# Sheet1.net
KiCad netlist of a schematic drawn in Altium Designer
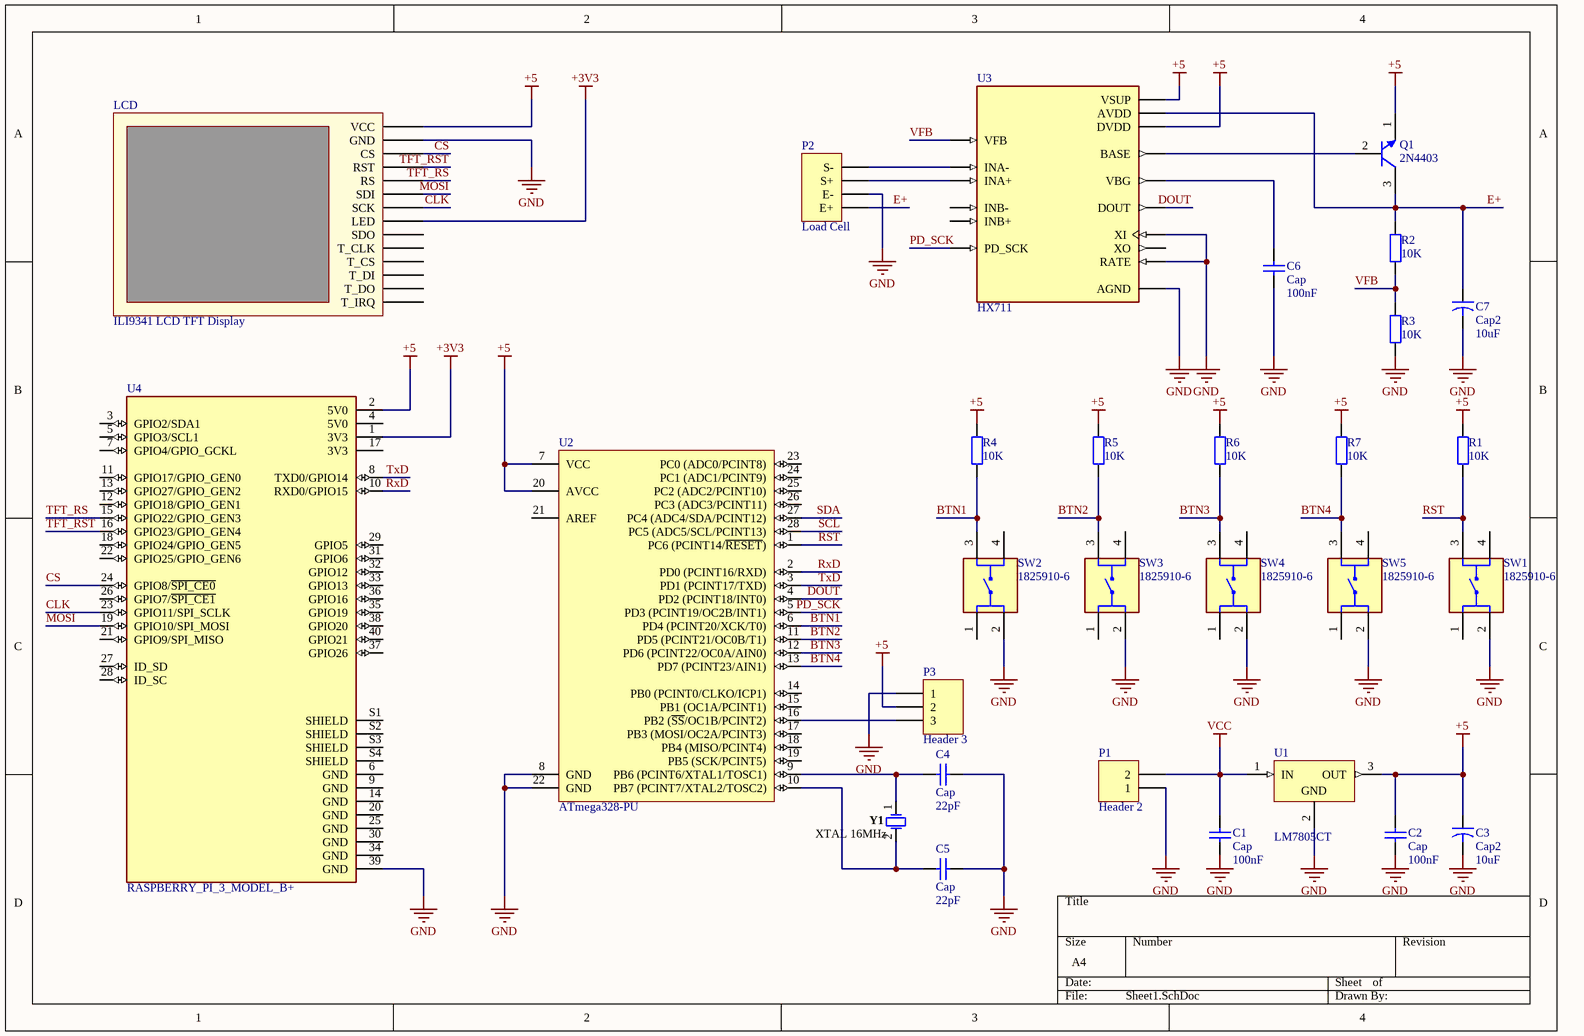
[diagram p0: Sheet1.SchDoc]

(export (version "E")
  (design (tool "Eeschema 10.0.6"))
  (components
    (comp (ref "C1")
      (value "Cap")
      (footprint "RAD-0.2")
      (description "Capacitor")
      (fields (field (name "ALTIUM_VALUE") "100nF") (field (name "PUBLISHER") "Altium Limited"))
      (libsource (lib "Miscellaneous Devices") (part "Cap"))
    )
    (comp (ref "C2")
      (value "Cap")
      (footprint "RAD-0.2")
      (description "Capacitor")
      (fields (field (name "ALTIUM_VALUE") "100nF") (field (name "PUBLISHER") "Altium Limited"))
      (libsource (lib "Miscellaneous Devices") (part "Cap"))
    )
    (comp (ref "C3")
      (value "Cap2")
      (footprint "R38")
      (description "Capacitor")
      (fields (field (name "ALTIUM_VALUE") "10uF") (field (name "PUBLISHER") "Altium Limited"))
      (libsource (lib "Miscellaneous Devices") (part "Cap2"))
    )
    (comp (ref "C4")
      (value "Cap")
      (footprint "RAD-0.1")
      (description "Capacitor")
      (fields (field (name "ALTIUM_VALUE") "22pF") (field (name "PUBLISHER") "Altium Limited"))
      (libsource (lib "Miscellaneous Devices") (part "Cap"))
    )
    (comp (ref "C5")
      (value "Cap")
      (footprint "RAD-0.1")
      (description "Capacitor")
      (fields (field (name "ALTIUM_VALUE") "22pF") (field (name "PUBLISHER") "Altium Limited"))
      (libsource (lib "Miscellaneous Devices") (part "Cap"))
    )
    (comp (ref "C6")
      (value "Cap")
      (footprint "RAD-0.2")
      (description "Capacitor")
      (fields (field (name "ALTIUM_VALUE") "100nF") (field (name "PUBLISHER") "Altium Limited"))
      (libsource (lib "Miscellaneous Devices") (part "Cap"))
    )
    (comp (ref "C7")
      (value "Cap2")
      (footprint "R38")
      (description "Capacitor")
      (fields (field (name "ALTIUM_VALUE") "10uF") (field (name "PUBLISHER") "Altium Limited"))
      (libsource (lib "Miscellaneous Devices") (part "Cap2"))
    )
    (comp (ref "LCD")
      (value "ILI9341 LCD TFT Display")
      (footprint "ILI9341")
      (libsource (lib "ILI9341") (part "ILI9341"))
    )
    (comp (ref "P1")
      (value "Header 2")
      (footprint "HDR1X2")
      (description "Header, 2-Pin")
      (fields (field (name "PUBLISHER") "Altium Limited"))
      (libsource (lib "Miscellaneous Connectors") (part "Header 2"))
    )
    (comp (ref "P2")
      (value "Load Cell")
      (footprint "HDR1X4")
      (description "Load Cell Connector, 4-Pin")
      (fields (field (name "PUBLISHER") "Altium Limited"))
      (libsource (lib "Miscellaneous Connectors") (part "Header 4"))
    )
    (comp (ref "P3")
      (value "Header 3")
      (footprint "HDR1X3")
      (description "Header, 3-Pin")
      (fields (field (name "PUBLISHER") "Altium Limited"))
      (libsource (lib "Miscellaneous Connectors") (part "Header 3"))
    )
    (comp (ref "Q1")
      (value "2N4403")
      (footprint "ONSC-TO-92-3-29-11_AM_BL")
      (description "General Purpose Transistor, NPN Silicon, 3-Pin TO-92, Pb-Free, Ammo Box")
      (fields (field (name "PARTNUMBER") "2N4401RLRPG") (field (name "MANUFACTURER") "On Semiconductor"))
      (libsource (lib "Altium Content Vault") (part "ONSC-NPN-E1B2C3-3"))
    )
    (comp (ref "R1")
      (value "10K")
      (footprint "AXIAL-0.4")
      (description "Resistor")
      (fields (field (name "PUBLISHER") "Altium Limited"))
      (libsource (lib "Miscellaneous Devices") (part "Res2"))
    )
    (comp (ref "R2")
      (value "10K")
      (footprint "AXIAL-0.4")
      (description "Resistor")
      (fields (field (name "PUBLISHER") "Altium Limited"))
      (libsource (lib "Miscellaneous Devices") (part "Res2"))
    )
    (comp (ref "R3")
      (value "10K")
      (footprint "AXIAL-0.4")
      (description "Resistor")
      (fields (field (name "PUBLISHER") "Altium Limited"))
      (libsource (lib "Miscellaneous Devices") (part "Res2"))
    )
    (comp (ref "R4")
      (value "10K")
      (footprint "AXIAL-0.4")
      (description "Resistor")
      (fields (field (name "PUBLISHER") "Altium Limited"))
      (libsource (lib "Miscellaneous Devices") (part "Res2"))
    )
    (comp (ref "R5")
      (value "10K")
      (footprint "AXIAL-0.4")
      (description "Resistor")
      (fields (field (name "PUBLISHER") "Altium Limited"))
      (libsource (lib "Miscellaneous Devices") (part "Res2"))
    )
    (comp (ref "R6")
      (value "10K")
      (footprint "AXIAL-0.4")
      (description "Resistor")
      (fields (field (name "PUBLISHER") "Altium Limited"))
      (libsource (lib "Miscellaneous Devices") (part "Res2"))
    )
    (comp (ref "R7")
      (value "10K")
      (footprint "AXIAL-0.4")
      (description "Resistor")
      (fields (field (name "PUBLISHER") "Altium Limited"))
      (libsource (lib "Miscellaneous Devices") (part "Res2"))
    )
    (comp (ref "SW1")
      (value "1825910-6")
      (footprint "SW_1825910-6-4")
      (description "Switch Tactile OFF (ON) SPST Round Button PC Pins 0.05A 24VDC 100000Cycles 1.57N Thru-Hole Loose")
      (libsource (lib "1825910-6") (part "1825910-6"))
    )
    (comp (ref "SW2")
      (value "1825910-6")
      (footprint "SW_1825910-6-4")
      (description "Switch Tactile OFF (ON) SPST Round Button PC Pins 0.05A 24VDC 100000Cycles 1.57N Thru-Hole Loose")
      (libsource (lib "1825910-6") (part "1825910-6"))
    )
    (comp (ref "SW3")
      (value "1825910-6")
      (footprint "SW_1825910-6-4")
      (description "Switch Tactile OFF (ON) SPST Round Button PC Pins 0.05A 24VDC 100000Cycles 1.57N Thru-Hole Loose")
      (libsource (lib "1825910-6") (part "1825910-6"))
    )
    (comp (ref "SW4")
      (value "1825910-6")
      (footprint "SW_1825910-6-4")
      (description "Switch Tactile OFF (ON) SPST Round Button PC Pins 0.05A 24VDC 100000Cycles 1.57N Thru-Hole Loose")
      (libsource (lib "1825910-6") (part "1825910-6"))
    )
    (comp (ref "SW5")
      (value "1825910-6")
      (footprint "SW_1825910-6-4")
      (description "Switch Tactile OFF (ON) SPST Round Button PC Pins 0.05A 24VDC 100000Cycles 1.57N Thru-Hole Loose")
      (libsource (lib "1825910-6") (part "1825910-6"))
    )
    (comp (ref "U1")
      (value "LM7805CT")
      (footprint "FAIR-TO-220-3")
      (description "Positive Voltage Regulator, 5 V, 1 A, -40 to 125 degC, 3-Pin TO-220, RoHS, Tube")
      (fields (field (name "MANUFACTURER") "FairchildSemiconductor"))
      (libsource (lib "Altium Content Vault") (part "FAIR-LM7805CT-TO220-3"))
    )
    (comp (ref "U2")
      (value "ATmega328-PU")
      (footprint "28P3")
      (libsource (lib "Altium Content Vault") (part "MC-8B-ATM48-IL28"))
    )
    (comp (ref "U3")
      (value "HX711")
      (footprint "SOP127P600X180-16N")
      (libsource (lib "HX711") (part "HX711"))
    )
    (comp (ref "U4")
      (value "RASPBERRY_PI_3_MODEL_B+")
      (footprint "MODULE_RASPBERRY_PI_3_MODEL_B+")
      (description "BCM2835 Raspberry Pi Model B+ - ARM11, VideoCore MPU Embedded Evaluation Board")
      (libsource (lib "RASPBERRY_PI_3_MODEL_B_") (part "RASPBERRY_PI_3_MODEL_B+"))
    )
    (comp (ref "Y1")
      (value "XTAL 16MHz")
      (footprint "FOX-FOXSLF-2_V")
      (description "Resistance Weld Thru-Hole Crystal, 12 MHz, +/-30 ppm, -20 to 70 degC, 2-Pin THD, RoHS, Bulk")
      (libsource (lib "Altium Content Vault") (part "XTAL-1-2-2"))
    )
  )
  (nets
    (net (code "1") (name "+3V3") (class "Default")
      (node (ref "LCD") (pin "7") (pinfunction "LED_7") (pintype "passive"))
      (node (ref "U4") (pin "1") (pinfunction "3V3_1") (pintype "power_in"))
    )
    (net (code "2") (name "+5") (class "Default")
      (node (ref "C2") (pin "2") (pinfunction "2_2") (pintype "passive"))
      (node (ref "C3") (pin "1") (pinfunction "1_1") (pintype "passive"))
      (node (ref "LCD") (pin "0") (pinfunction "VCC_0") (pintype "passive"))
      (node (ref "P3") (pin "2") (pinfunction "2_2") (pintype "passive"))
      (node (ref "Q1") (pin "1") (pinfunction "E_1") (pintype "passive"))
      (node (ref "R1") (pin "2") (pinfunction "2_2") (pintype "passive"))
      (node (ref "R4") (pin "2") (pinfunction "2_2") (pintype "passive"))
      (node (ref "R5") (pin "2") (pinfunction "2_2") (pintype "passive"))
      (node (ref "R6") (pin "2") (pinfunction "2_2") (pintype "passive"))
      (node (ref "R7") (pin "2") (pinfunction "2_2") (pintype "passive"))
      (node (ref "U1") (pin "3") (pinfunction "OUT_3") (pintype "output"))
      (node (ref "U2") (pin "20") (pinfunction "AVCC_20") (pintype "power_in"))
      (node (ref "U2") (pin "7") (pinfunction "VCC_7") (pintype "power_in"))
      (node (ref "U3") (pin "1") (pinfunction "VSUP_1") (pintype "power_in"))
      (node (ref "U3") (pin "16") (pinfunction "DVDD_16") (pintype "power_in"))
      (node (ref "U4") (pin "2") (pinfunction "5V0_2") (pintype "power_in"))
    )
    (net (code "3") (name "/BTN1") (class "Default")
      (node (ref "R4") (pin "1") (pinfunction "1_1") (pintype "passive"))
      (node (ref "SW2") (pin "3") (pinfunction "3_3") (pintype "passive"))
      (node (ref "U2") (pin "6") (pinfunction "PD4_(PCINT20/XCK/T0)_6") (pintype "bidirectional"))
    )
    (net (code "4") (name "/BTN2") (class "Default")
      (node (ref "R5") (pin "1") (pinfunction "1_1") (pintype "passive"))
      (node (ref "SW3") (pin "3") (pinfunction "3_3") (pintype "passive"))
      (node (ref "U2") (pin "11") (pinfunction "PD5_(PCINT21/OC0B/T1)_11") (pintype "bidirectional"))
    )
    (net (code "5") (name "/BTN3") (class "Default")
      (node (ref "R6") (pin "1") (pinfunction "1_1") (pintype "passive"))
      (node (ref "SW4") (pin "3") (pinfunction "3_3") (pintype "passive"))
      (node (ref "U2") (pin "12") (pinfunction "PD6_(PCINT22/OC0A/AIN0)_12") (pintype "bidirectional"))
    )
    (net (code "6") (name "/BTN4") (class "Default")
      (node (ref "R7") (pin "1") (pinfunction "1_1") (pintype "passive"))
      (node (ref "SW5") (pin "3") (pinfunction "3_3") (pintype "passive"))
      (node (ref "U2") (pin "13") (pinfunction "PD7_(PCINT23/AIN1)_13") (pintype "bidirectional"))
    )
    (net (code "7") (name "/CLK") (class "Default")
      (node (ref "LCD") (pin "6") (pinfunction "SCK_6") (pintype "passive"))
      (node (ref "U4") (pin "23") (pinfunction "GPIO11/SPI_SCLK_23") (pintype "bidirectional"))
    )
    (net (code "8") (name "/CS") (class "Default")
      (node (ref "LCD") (pin "2") (pinfunction "CS_2") (pintype "passive"))
      (node (ref "U4") (pin "24") (pinfunction "GPIO8/~{SPI_CE0}_24") (pintype "bidirectional"))
    )
    (net (code "9") (name "/DOUT") (class "Default")
      (node (ref "U2") (pin "4") (pinfunction "PD2_(PCINT18/INT0)_4") (pintype "bidirectional"))
      (node (ref "U3") (pin "12") (pinfunction "DOUT_12") (pintype "output"))
    )
    (net (code "10") (name "/E+") (class "Default")
      (node (ref "C7") (pin "1") (pinfunction "1_1") (pintype "passive"))
      (node (ref "P2") (pin "1") (pinfunction "E+_1") (pintype "passive"))
      (node (ref "Q1") (pin "3") (pinfunction "C_3") (pintype "passive"))
      (node (ref "R2") (pin "2") (pinfunction "2_2") (pintype "passive"))
      (node (ref "U3") (pin "3") (pinfunction "AVDD_3") (pintype "power_in"))
    )
    (net (code "11") (name "/MOSI") (class "Default")
      (node (ref "LCD") (pin "5") (pinfunction "SDI_5") (pintype "passive"))
      (node (ref "U4") (pin "19") (pinfunction "GPIO10/SPI_MOSI_19") (pintype "bidirectional"))
    )
    (net (code "12") (name "/PD_SCK") (class "Default")
      (node (ref "U2") (pin "5") (pinfunction "PD3_(PCINT19/OC2B/INT1)_5") (pintype "bidirectional"))
      (node (ref "U3") (pin "11") (pinfunction "PD_SCK_11") (pintype "input"))
    )
    (net (code "13") (name "/RST") (class "Default")
      (node (ref "R1") (pin "1") (pinfunction "1_1") (pintype "passive"))
      (node (ref "SW1") (pin "3") (pinfunction "3_3") (pintype "passive"))
      (node (ref "U2") (pin "1") (pinfunction "PC6_(PCINT14/~{RESET})_1") (pintype "bidirectional"))
    )
    (net (code "14") (name "/RxD") (class "Default")
      (node (ref "U2") (pin "2") (pinfunction "PD0_(PCINT16/RXD)_2") (pintype "bidirectional"))
      (node (ref "U4") (pin "10") (pinfunction "RXD0/GPIO15_10") (pintype "bidirectional"))
    )
    (net (code "15") (name "/SCL") (class "Default")
      (node (ref "U2") (pin "28") (pinfunction "PC5_(ADC5/SCL/PCINT13)_28") (pintype "bidirectional"))
    )
    (net (code "16") (name "/SDA") (class "Default")
      (node (ref "U2") (pin "27") (pinfunction "PC4_(ADC4/SDA/PCINT12)_27") (pintype "bidirectional"))
    )
    (net (code "17") (name "/TFT_RS") (class "Default")
      (node (ref "LCD") (pin "4") (pinfunction "RS_4") (pintype "passive"))
      (node (ref "U4") (pin "15") (pinfunction "GPIO22/GPIO_GEN3_15") (pintype "bidirectional"))
    )
    (net (code "18") (name "/TFT_RST") (class "Default")
      (node (ref "LCD") (pin "3") (pinfunction "RST_3") (pintype "passive"))
      (node (ref "U4") (pin "16") (pinfunction "GPIO23/GPIO_GEN4_16") (pintype "bidirectional"))
    )
    (net (code "19") (name "/TxD") (class "Default")
      (node (ref "U2") (pin "3") (pinfunction "PD1_(PCINT17/TXD)_3") (pintype "bidirectional"))
      (node (ref "U4") (pin "8") (pinfunction "TXD0/GPIO14_8") (pintype "bidirectional"))
    )
    (net (code "20") (name "/VFB") (class "Default")
      (node (ref "R2") (pin "1") (pinfunction "1_1") (pintype "passive"))
      (node (ref "R3") (pin "2") (pinfunction "2_2") (pintype "passive"))
      (node (ref "U3") (pin "4") (pinfunction "VFB_4") (pintype "input"))
    )
    (net (code "21") (name "GND") (class "Default")
      (node (ref "C1") (pin "1") (pinfunction "1_1") (pintype "passive"))
      (node (ref "C2") (pin "1") (pinfunction "1_1") (pintype "passive"))
      (node (ref "C3") (pin "2") (pinfunction "2_2") (pintype "passive"))
      (node (ref "C4") (pin "2") (pinfunction "2_2") (pintype "passive"))
      (node (ref "C5") (pin "2") (pinfunction "2_2") (pintype "passive"))
      (node (ref "C6") (pin "1") (pinfunction "1_1") (pintype "passive"))
      (node (ref "C7") (pin "2") (pinfunction "2_2") (pintype "passive"))
      (node (ref "LCD") (pin "1") (pinfunction "GND_1") (pintype "passive"))
      (node (ref "P1") (pin "1") (pinfunction "1_1") (pintype "passive"))
      (node (ref "P2") (pin "2") (pinfunction "E-_2") (pintype "passive"))
      (node (ref "P3") (pin "1") (pinfunction "1_1") (pintype "passive"))
      (node (ref "R3") (pin "1") (pinfunction "1_1") (pintype "passive"))
      (node (ref "SW1") (pin "2") (pinfunction "2_2") (pintype "passive"))
      (node (ref "SW2") (pin "2") (pinfunction "2_2") (pintype "passive"))
      (node (ref "SW3") (pin "2") (pinfunction "2_2") (pintype "passive"))
      (node (ref "SW4") (pin "2") (pinfunction "2_2") (pintype "passive"))
      (node (ref "SW5") (pin "2") (pinfunction "2_2") (pintype "passive"))
      (node (ref "U1") (pin "2") (pinfunction "GND_2") (pintype "power_in"))
      (node (ref "U2") (pin "22") (pinfunction "GND_22") (pintype "power_in"))
      (node (ref "U2") (pin "8") (pinfunction "GND_8") (pintype "power_in"))
      (node (ref "U3") (pin "14") (pinfunction "XI_14") (pintype "input"))
      (node (ref "U3") (pin "15") (pinfunction "RATE_15") (pintype "input"))
      (node (ref "U3") (pin "5") (pinfunction "AGND_5") (pintype "power_in"))
      (node (ref "U4") (pin "39") (pinfunction "GND_39") (pintype "power_in"))
    )
    (net (code "22") (name "Net-(P2-S+)") (class "Default")
      (node (ref "P2") (pin "3") (pinfunction "S+_3") (pintype "passive"))
      (node (ref "U3") (pin "8") (pinfunction "INA+_8") (pintype "input"))
    )
    (net (code "23") (name "Net-(P2-S-)") (class "Default")
      (node (ref "P2") (pin "4") (pinfunction "S-_4") (pintype "passive"))
      (node (ref "U3") (pin "7") (pinfunction "INA-_7") (pintype "input"))
    )
    (net (code "24") (name "Net-(Q1-B)") (class "Default")
      (node (ref "Q1") (pin "2") (pinfunction "B_2") (pintype "passive"))
      (node (ref "U3") (pin "2") (pinfunction "BASE_2") (pintype "output"))
    )
    (net (code "25") (name "Net-(U2-PB2_(~{SS}{slash}OC1B{slash}PCINT2))") (class "Default")
      (node (ref "P3") (pin "3") (pinfunction "3_3") (pintype "passive"))
      (node (ref "U2") (pin "16") (pinfunction "PB2_(~{SS}/OC1B/PCINT2)_16") (pintype "bidirectional"))
    )
    (net (code "26") (name "Net-(U2-PB6_(PCINT6{slash}XTAL1{slash}TOSC1))") (class "Default")
      (node (ref "C4") (pin "1") (pinfunction "1_1") (pintype "passive"))
      (node (ref "U2") (pin "9") (pinfunction "PB6_(PCINT6/XTAL1/TOSC1)_9") (pintype "bidirectional"))
      (node (ref "Y1") (pin "1") (pinfunction "1_1") (pintype "passive"))
    )
    (net (code "27") (name "Net-(U2-PB7_(PCINT7{slash}XTAL2{slash}TOSC2))") (class "Default")
      (node (ref "C5") (pin "1") (pinfunction "1_1") (pintype "passive"))
      (node (ref "U2") (pin "10") (pinfunction "PB7_(PCINT7/XTAL2/TOSC2)_10") (pintype "bidirectional"))
      (node (ref "Y1") (pin "2") (pinfunction "2_2") (pintype "passive"))
    )
    (net (code "28") (name "Net-(U3-VBG)") (class "Default")
      (node (ref "C6") (pin "2") (pinfunction "2_2") (pintype "passive"))
      (node (ref "U3") (pin "6") (pinfunction "VBG_6") (pintype "output"))
    )
    (net (code "29") (name "VCC") (class "Default")
      (node (ref "C1") (pin "2") (pinfunction "2_2") (pintype "passive"))
      (node (ref "P1") (pin "2") (pinfunction "2_2") (pintype "passive"))
      (node (ref "U1") (pin "1") (pinfunction "IN_1") (pintype "input"))
    )
    (net (code "30") (name "unconnected-(LCD-SDO-Pad8)") (class "Default")
      (node (ref "LCD") (pin "8") (pinfunction "SDO_8") (pintype "passive"))
    )
    (net (code "31") (name "unconnected-(LCD-T_CLK-Pad9)") (class "Default")
      (node (ref "LCD") (pin "9") (pinfunction "T_CLK_9") (pintype "passive"))
    )
    (net (code "32") (name "unconnected-(LCD-T_CS-Pad10)") (class "Default")
      (node (ref "LCD") (pin "10") (pinfunction "T_CS_10") (pintype "passive"))
    )
    (net (code "33") (name "unconnected-(LCD-T_DI-Pad11)") (class "Default")
      (node (ref "LCD") (pin "11") (pinfunction "T_DI_11") (pintype "passive"))
    )
    (net (code "34") (name "unconnected-(LCD-T_DO-Pad12)") (class "Default")
      (node (ref "LCD") (pin "12") (pinfunction "T_DO_12") (pintype "passive"))
    )
    (net (code "35") (name "unconnected-(LCD-T_IRQ-Pad13)") (class "Default")
      (node (ref "LCD") (pin "13") (pinfunction "T_IRQ_13") (pintype "passive"))
    )
    (net (code "36") (name "unconnected-(SW1-Pad1)") (class "Default")
      (node (ref "SW1") (pin "1") (pinfunction "1_1") (pintype "passive"))
    )
    (net (code "37") (name "unconnected-(SW1-Pad4)") (class "Default")
      (node (ref "SW1") (pin "4") (pinfunction "4_4") (pintype "passive"))
    )
    (net (code "38") (name "unconnected-(SW2-Pad1)") (class "Default")
      (node (ref "SW2") (pin "1") (pinfunction "1_1") (pintype "passive"))
    )
    (net (code "39") (name "unconnected-(SW2-Pad4)") (class "Default")
      (node (ref "SW2") (pin "4") (pinfunction "4_4") (pintype "passive"))
    )
    (net (code "40") (name "unconnected-(SW3-Pad1)") (class "Default")
      (node (ref "SW3") (pin "1") (pinfunction "1_1") (pintype "passive"))
    )
    (net (code "41") (name "unconnected-(SW3-Pad4)") (class "Default")
      (node (ref "SW3") (pin "4") (pinfunction "4_4") (pintype "passive"))
    )
    (net (code "42") (name "unconnected-(SW4-Pad1)") (class "Default")
      (node (ref "SW4") (pin "1") (pinfunction "1_1") (pintype "passive"))
    )
    (net (code "43") (name "unconnected-(SW4-Pad4)") (class "Default")
      (node (ref "SW4") (pin "4") (pinfunction "4_4") (pintype "passive"))
    )
    (net (code "44") (name "unconnected-(SW5-Pad1)") (class "Default")
      (node (ref "SW5") (pin "1") (pinfunction "1_1") (pintype "passive"))
    )
    (net (code "45") (name "unconnected-(SW5-Pad4)") (class "Default")
      (node (ref "SW5") (pin "4") (pinfunction "4_4") (pintype "passive"))
    )
    (net (code "46") (name "unconnected-(U2-AREF-Pad21)") (class "Default")
      (node (ref "U2") (pin "21") (pinfunction "AREF_21") (pintype "power_in"))
    )
    (net (code "47") (name "unconnected-(U2-PB0_(PCINT0{slash}CLKO{slash}ICP1)-Pad14)") (class "Default")
      (node (ref "U2") (pin "14") (pinfunction "PB0_(PCINT0/CLKO/ICP1)_14") (pintype "bidirectional"))
    )
    (net (code "48") (name "unconnected-(U2-PB1_(OC1A{slash}PCINT1)-Pad15)") (class "Default")
      (node (ref "U2") (pin "15") (pinfunction "PB1_(OC1A/PCINT1)_15") (pintype "bidirectional"))
    )
    (net (code "49") (name "unconnected-(U2-PB3_(MOSI{slash}OC2A{slash}PCINT3)-Pad17)") (class "Default")
      (node (ref "U2") (pin "17") (pinfunction "PB3_(MOSI/OC2A/PCINT3)_17") (pintype "bidirectional"))
    )
    (net (code "50") (name "unconnected-(U2-PB4_(MISO{slash}PCINT4)-Pad18)") (class "Default")
      (node (ref "U2") (pin "18") (pinfunction "PB4_(MISO/PCINT4)_18") (pintype "bidirectional"))
    )
    (net (code "51") (name "unconnected-(U2-PB5_(SCK{slash}PCINT5)-Pad19)") (class "Default")
      (node (ref "U2") (pin "19") (pinfunction "PB5_(SCK/PCINT5)_19") (pintype "bidirectional"))
    )
    (net (code "52") (name "unconnected-(U2-PC0_(ADC0{slash}PCINT8)-Pad23)") (class "Default")
      (node (ref "U2") (pin "23") (pinfunction "PC0_(ADC0/PCINT8)_23") (pintype "bidirectional"))
    )
    (net (code "53") (name "unconnected-(U2-PC1_(ADC1{slash}PCINT9)-Pad24)") (class "Default")
      (node (ref "U2") (pin "24") (pinfunction "PC1_(ADC1/PCINT9)_24") (pintype "bidirectional"))
    )
    (net (code "54") (name "unconnected-(U2-PC2_(ADC2{slash}PCINT10)-Pad25)") (class "Default")
      (node (ref "U2") (pin "25") (pinfunction "PC2_(ADC2/PCINT10)_25") (pintype "bidirectional"))
    )
    (net (code "55") (name "unconnected-(U2-PC3_(ADC3{slash}PCINT11)-Pad26)") (class "Default")
      (node (ref "U2") (pin "26") (pinfunction "PC3_(ADC3/PCINT11)_26") (pintype "bidirectional"))
    )
    (net (code "56") (name "unconnected-(U3-INB+-Pad10)") (class "Default")
      (node (ref "U3") (pin "10") (pinfunction "INB+_10") (pintype "input"))
    )
    (net (code "57") (name "unconnected-(U3-INB--Pad9)") (class "Default")
      (node (ref "U3") (pin "9") (pinfunction "INB-_9") (pintype "input"))
    )
    (net (code "58") (name "unconnected-(U3-XO-Pad13)") (class "Default")
      (node (ref "U3") (pin "13") (pinfunction "XO_13") (pintype "output"))
    )
    (net (code "59") (name "unconnected-(U4-3V3-Pad17)") (class "Default")
      (node (ref "U4") (pin "17") (pinfunction "3V3_17") (pintype "power_in"))
    )
    (net (code "60") (name "unconnected-(U4-5V0-Pad4)") (class "Default")
      (node (ref "U4") (pin "4") (pinfunction "5V0_4") (pintype "power_in"))
    )
    (net (code "61") (name "unconnected-(U4-GND-Pad6)") (class "Default")
      (node (ref "U4") (pin "6") (pinfunction "GND_6") (pintype "power_in"))
    )
    (net (code "62") (name "unconnected-(U4-GND-Pad9)") (class "Default")
      (node (ref "U4") (pin "9") (pinfunction "GND_9") (pintype "power_in"))
    )
    (net (code "63") (name "unconnected-(U4-GND-Pad14)") (class "Default")
      (node (ref "U4") (pin "14") (pinfunction "GND_14") (pintype "power_in"))
    )
    (net (code "64") (name "unconnected-(U4-GND-Pad20)") (class "Default")
      (node (ref "U4") (pin "20") (pinfunction "GND_20") (pintype "power_in"))
    )
    (net (code "65") (name "unconnected-(U4-GND-Pad25)") (class "Default")
      (node (ref "U4") (pin "25") (pinfunction "GND_25") (pintype "power_in"))
    )
    (net (code "66") (name "unconnected-(U4-GND-Pad30)") (class "Default")
      (node (ref "U4") (pin "30") (pinfunction "GND_30") (pintype "power_in"))
    )
    (net (code "67") (name "unconnected-(U4-GND-Pad34)") (class "Default")
      (node (ref "U4") (pin "34") (pinfunction "GND_34") (pintype "power_in"))
    )
    (net (code "68") (name "unconnected-(U4-GPIO2{slash}SDA1-Pad3)") (class "Default")
      (node (ref "U4") (pin "3") (pinfunction "GPIO2/SDA1_3") (pintype "bidirectional"))
    )
    (net (code "69") (name "unconnected-(U4-GPIO3{slash}SCL1-Pad5)") (class "Default")
      (node (ref "U4") (pin "5") (pinfunction "GPIO3/SCL1_5") (pintype "bidirectional"))
    )
    (net (code "70") (name "unconnected-(U4-GPIO4{slash}GPIO_GCKL-Pad7)") (class "Default")
      (node (ref "U4") (pin "7") (pinfunction "GPIO4/GPIO_GCKL_7") (pintype "bidirectional"))
    )
    (net (code "71") (name "unconnected-(U4-GPIO5-Pad29)") (class "Default")
      (node (ref "U4") (pin "29") (pinfunction "GPIO5_29") (pintype "bidirectional"))
    )
    (net (code "72") (name "unconnected-(U4-GPIO6-Pad31)") (class "Default")
      (node (ref "U4") (pin "31") (pinfunction "GPIO6_31") (pintype "bidirectional"))
    )
    (net (code "73") (name "unconnected-(U4-GPIO7{slash}~{SPI_CE1}-Pad26)") (class "Default")
      (node (ref "U4") (pin "26") (pinfunction "GPIO7/~{SPI_CE1}_26") (pintype "bidirectional"))
    )
    (net (code "74") (name "unconnected-(U4-GPIO9{slash}SPI_MISO-Pad21)") (class "Default")
      (node (ref "U4") (pin "21") (pinfunction "GPIO9/SPI_MISO_21") (pintype "bidirectional"))
    )
    (net (code "75") (name "unconnected-(U4-GPIO12-Pad32)") (class "Default")
      (node (ref "U4") (pin "32") (pinfunction "GPIO12_32") (pintype "bidirectional"))
    )
    (net (code "76") (name "unconnected-(U4-GPIO13-Pad33)") (class "Default")
      (node (ref "U4") (pin "33") (pinfunction "GPIO13_33") (pintype "bidirectional"))
    )
    (net (code "77") (name "unconnected-(U4-GPIO16-Pad36)") (class "Default")
      (node (ref "U4") (pin "36") (pinfunction "GPIO16_36") (pintype "bidirectional"))
    )
    (net (code "78") (name "unconnected-(U4-GPIO17{slash}GPIO_GEN0-Pad11)") (class "Default")
      (node (ref "U4") (pin "11") (pinfunction "GPIO17/GPIO_GEN0_11") (pintype "bidirectional"))
    )
    (net (code "79") (name "unconnected-(U4-GPIO18{slash}GPIO_GEN1-Pad12)") (class "Default")
      (node (ref "U4") (pin "12") (pinfunction "GPIO18/GPIO_GEN1_12") (pintype "bidirectional"))
    )
    (net (code "80") (name "unconnected-(U4-GPIO19-Pad35)") (class "Default")
      (node (ref "U4") (pin "35") (pinfunction "GPIO19_35") (pintype "bidirectional"))
    )
    (net (code "81") (name "unconnected-(U4-GPIO20-Pad38)") (class "Default")
      (node (ref "U4") (pin "38") (pinfunction "GPIO20_38") (pintype "bidirectional"))
    )
    (net (code "82") (name "unconnected-(U4-GPIO21-Pad40)") (class "Default")
      (node (ref "U4") (pin "40") (pinfunction "GPIO21_40") (pintype "bidirectional"))
    )
    (net (code "83") (name "unconnected-(U4-GPIO24{slash}GPIO_GEN5-Pad18)") (class "Default")
      (node (ref "U4") (pin "18") (pinfunction "GPIO24/GPIO_GEN5_18") (pintype "bidirectional"))
    )
    (net (code "84") (name "unconnected-(U4-GPIO25{slash}GPIO_GEN6-Pad22)") (class "Default")
      (node (ref "U4") (pin "22") (pinfunction "GPIO25/GPIO_GEN6_22") (pintype "bidirectional"))
    )
    (net (code "85") (name "unconnected-(U4-GPIO26-Pad37)") (class "Default")
      (node (ref "U4") (pin "37") (pinfunction "GPIO26_37") (pintype "bidirectional"))
    )
    (net (code "86") (name "unconnected-(U4-GPIO27{slash}GPIO_GEN2-Pad13)") (class "Default")
      (node (ref "U4") (pin "13") (pinfunction "GPIO27/GPIO_GEN2_13") (pintype "bidirectional"))
    )
    (net (code "87") (name "unconnected-(U4-ID_SC-Pad28)") (class "Default")
      (node (ref "U4") (pin "28") (pinfunction "ID_SC_28") (pintype "bidirectional"))
    )
    (net (code "88") (name "unconnected-(U4-ID_SD-Pad27)") (class "Default")
      (node (ref "U4") (pin "27") (pinfunction "ID_SD_27") (pintype "bidirectional"))
    )
    (net (code "89") (name "unconnected-(U4-SHIELD-PadS1)") (class "Default")
      (node (ref "U4") (pin "S1") (pinfunction "SHIELD_S1") (pintype "power_in"))
    )
    (net (code "90") (name "unconnected-(U4-SHIELD-PadS2)") (class "Default")
      (node (ref "U4") (pin "S2") (pinfunction "SHIELD_S2") (pintype "power_in"))
    )
    (net (code "91") (name "unconnected-(U4-SHIELD-PadS3)") (class "Default")
      (node (ref "U4") (pin "S3") (pinfunction "SHIELD_S3") (pintype "power_in"))
    )
    (net (code "92") (name "unconnected-(U4-SHIELD-PadS4)") (class "Default")
      (node (ref "U4") (pin "S4") (pinfunction "SHIELD_S4") (pintype "power_in"))
    )
  )
)
